# PC0_Codec.net
KiCad netlist of a schematic drawn in Altium Designer
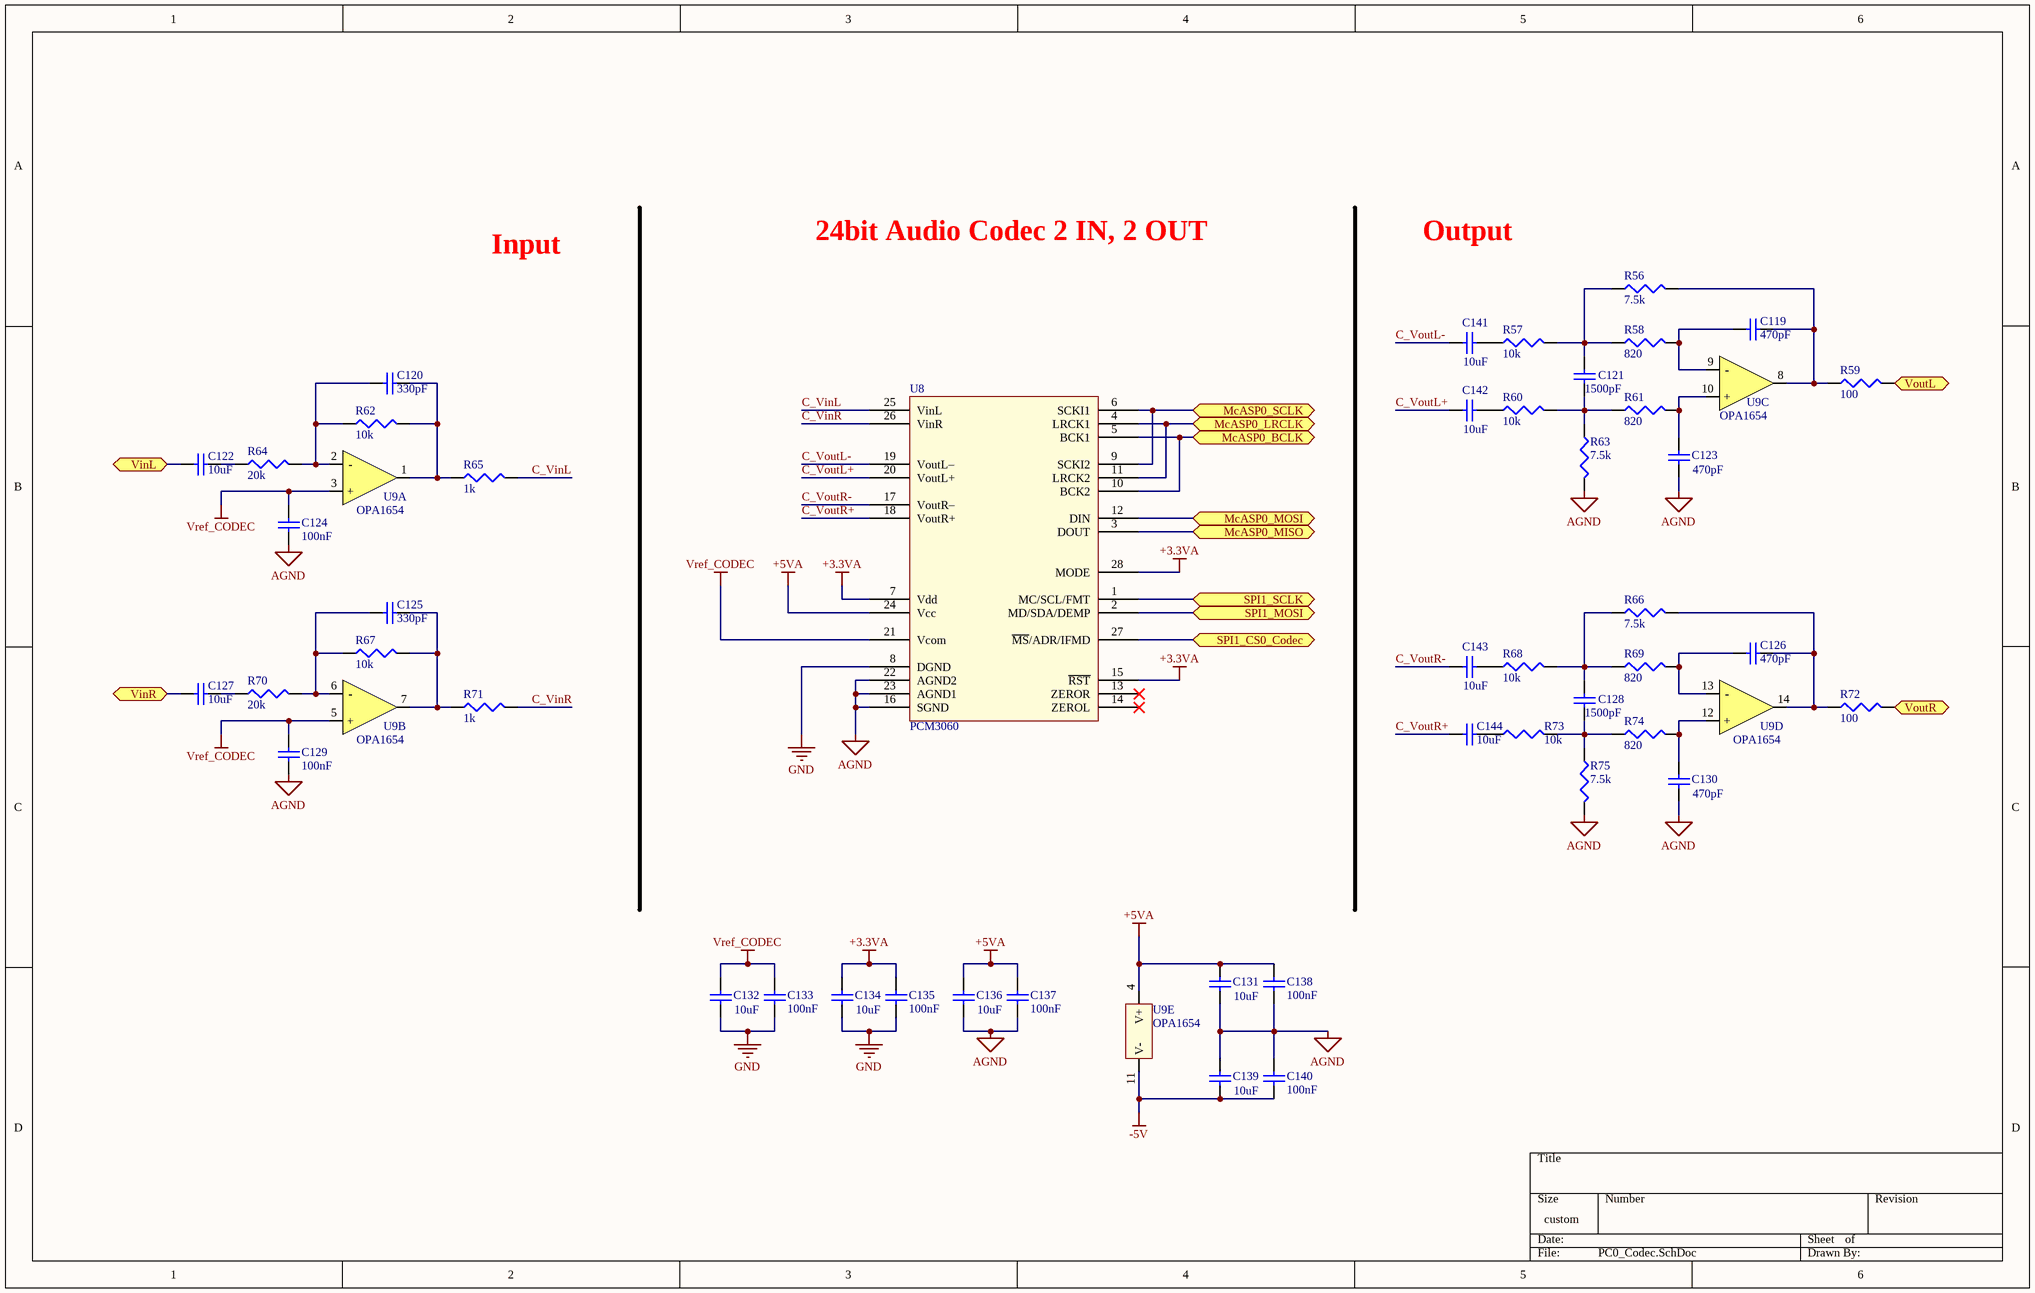
[diagram p0: PC0_Codec.SchDoc]

(export (version "E")
  (design (tool "Eeschema 10.0.6"))
  (components
    (comp (ref "C119")
      (value "470pF")
      (footprint "CAPC1608X08")
      (description "Capacitor")
      (fields (field (name "Comment") "Cap 470pF"))
      (libsource (lib "Michel") (part "Cap Semi"))
    )
    (comp (ref "C120")
      (value "330pF")
      (footprint "CAPC1608X08")
      (description "Capacitor")
      (fields (field (name "Comment") "Cap 330pF"))
      (libsource (lib "Michel") (part "Cap Semi"))
    )
    (comp (ref "C121")
      (value "1500pF")
      (footprint "CAPC1608X08")
      (description "Capacitor")
      (fields (field (name "Comment") "Cap 1500pF"))
      (libsource (lib "Michel") (part "Cap Semi"))
    )
    (comp (ref "C122")
      (value "10uF")
      (footprint "CAPC1608X08")
      (description "Capacitor")
      (fields (field (name "Comment") "Cap 10uF"))
      (libsource (lib "Michel") (part "Cap Semi"))
    )
    (comp (ref "C123")
      (value "470pF")
      (footprint "CAPC1608X08")
      (description "Capacitor")
      (fields (field (name "Comment") "Cap 470pF"))
      (libsource (lib "Michel") (part "Cap Semi"))
    )
    (comp (ref "C124")
      (value "100nF")
      (footprint "CAPC1608X08")
      (description "Capacitor")
      (fields (field (name "Comment") "Cap 100nF"))
      (libsource (lib "Michel") (part "Cap Semi"))
    )
    (comp (ref "C125")
      (value "330pF")
      (footprint "CAPC1608X08")
      (description "Capacitor")
      (fields (field (name "Comment") "Cap 330pF"))
      (libsource (lib "Michel") (part "Cap Semi"))
    )
    (comp (ref "C126")
      (value "470pF")
      (footprint "CAPC1608X08")
      (description "Capacitor")
      (fields (field (name "Comment") "Cap 470pF"))
      (libsource (lib "Michel") (part "Cap Semi"))
    )
    (comp (ref "C127")
      (value "10uF")
      (footprint "CAPC1608X08")
      (description "Capacitor")
      (fields (field (name "Comment") "Cap 10uF"))
      (libsource (lib "Michel") (part "Cap Semi"))
    )
    (comp (ref "C128")
      (value "1500pF")
      (footprint "CAPC1608X08")
      (description "Capacitor")
      (fields (field (name "Comment") "Cap 1500pF"))
      (libsource (lib "Michel") (part "Cap Semi"))
    )
    (comp (ref "C129")
      (value "100nF")
      (footprint "CAPC1608X08")
      (description "Capacitor")
      (fields (field (name "Comment") "Cap 100nF"))
      (libsource (lib "Michel") (part "Cap Semi"))
    )
    (comp (ref "C130")
      (value "470pF")
      (footprint "CAPC1608X08")
      (description "Capacitor")
      (fields (field (name "Comment") "Cap 470pF"))
      (libsource (lib "Michel") (part "Cap Semi"))
    )
    (comp (ref "C131")
      (value "10uF")
      (footprint "CAPC1608X08")
      (description "Capacitor")
      (fields (field (name "Comment") "Cap 10uF"))
      (libsource (lib "Michel") (part "Cap Semi"))
    )
    (comp (ref "C132")
      (value "10uF")
      (footprint "CAPC1608X08")
      (description "Capacitor")
      (fields (field (name "Comment") "Cap 10uF"))
      (libsource (lib "Michel") (part "Cap Semi"))
    )
    (comp (ref "C133")
      (value "100nF")
      (footprint "CAPC1608X08")
      (description "Capacitor")
      (fields (field (name "Comment") "Cap 100nF"))
      (libsource (lib "Michel") (part "Cap Semi"))
    )
    (comp (ref "C134")
      (value "10uF")
      (footprint "CAPC1608X08")
      (description "Capacitor")
      (fields (field (name "Comment") "Cap 10uF"))
      (libsource (lib "Michel") (part "Cap Semi"))
    )
    (comp (ref "C135")
      (value "100nF")
      (footprint "CAPC1608X08")
      (description "Capacitor")
      (fields (field (name "Comment") "Cap 100nF"))
      (libsource (lib "Michel") (part "Cap Semi"))
    )
    (comp (ref "C136")
      (value "10uF")
      (footprint "CAPC1608X08")
      (description "Capacitor")
      (fields (field (name "Comment") "Cap 10uF"))
      (libsource (lib "Michel") (part "Cap Semi"))
    )
    (comp (ref "C137")
      (value "100nF")
      (footprint "CAPC1608X08")
      (description "Capacitor")
      (fields (field (name "Comment") "Cap 100nF"))
      (libsource (lib "Michel") (part "Cap Semi"))
    )
    (comp (ref "C138")
      (value "100nF")
      (footprint "CAPC1608X08")
      (description "Capacitor")
      (fields (field (name "Comment") "Cap 100nF"))
      (libsource (lib "Michel") (part "Cap Semi"))
    )
    (comp (ref "C139")
      (value "10uF")
      (footprint "CAPC1608X08")
      (description "Capacitor")
      (fields (field (name "Comment") "Cap 10uF"))
      (libsource (lib "Michel") (part "Cap Semi"))
    )
    (comp (ref "C140")
      (value "100nF")
      (footprint "CAPC1608X08")
      (description "Capacitor")
      (fields (field (name "Comment") "Cap 100nF"))
      (libsource (lib "Michel") (part "Cap Semi"))
    )
    (comp (ref "C141")
      (value "10uF")
      (footprint "CAPC1608X08")
      (description "Capacitor")
      (fields (field (name "Comment") "Cap 10uF"))
      (libsource (lib "Michel") (part "Cap Semi"))
    )
    (comp (ref "C142")
      (value "10uF")
      (footprint "CAPC1608X08")
      (description "Capacitor")
      (fields (field (name "Comment") "Cap 10uF"))
      (libsource (lib "Michel") (part "Cap Semi"))
    )
    (comp (ref "C143")
      (value "10uF")
      (footprint "CAPC1608X08")
      (description "Capacitor")
      (fields (field (name "Comment") "Cap 10uF"))
      (libsource (lib "Michel") (part "Cap Semi"))
    )
    (comp (ref "C144")
      (value "10uF")
      (footprint "CAPC1608X08")
      (description "Capacitor")
      (fields (field (name "Comment") "Cap 10uF"))
      (libsource (lib "Michel") (part "Cap Semi"))
    )
    (comp (ref "R56")
      (value "7.5k")
      (footprint "RESC1608X05")
      (description "Resistor")
      (fields (field (name "Comment") "Res 7.5k"))
      (libsource (lib "Michel") (part "Res3"))
    )
    (comp (ref "R57")
      (value "10k")
      (footprint "RESC1608X05")
      (description "Resistor")
      (fields (field (name "Comment") "Res 10k"))
      (libsource (lib "Michel") (part "Res3"))
    )
    (comp (ref "R58")
      (value "820")
      (footprint "RESC1608X05")
      (description "Resistor")
      (fields (field (name "Comment") "Res 820"))
      (libsource (lib "Michel") (part "Res3"))
    )
    (comp (ref "R59")
      (value "100")
      (footprint "RESC1608X05")
      (description "Resistor")
      (fields (field (name "Comment") "Res 100"))
      (libsource (lib "Michel") (part "Res3"))
    )
    (comp (ref "R60")
      (value "10k")
      (footprint "RESC1608X05")
      (description "Resistor")
      (fields (field (name "Comment") "Res 10k"))
      (libsource (lib "Michel") (part "Res3"))
    )
    (comp (ref "R61")
      (value "820")
      (footprint "RESC1608X05")
      (description "Resistor")
      (fields (field (name "Comment") "Res 820"))
      (libsource (lib "Michel") (part "Res3"))
    )
    (comp (ref "R62")
      (value "10k")
      (footprint "RESC1608X05")
      (description "Resistor")
      (fields (field (name "Comment") "Res 10k"))
      (libsource (lib "Michel") (part "Res3"))
    )
    (comp (ref "R63")
      (value "7.5k")
      (footprint "RESC1608X05")
      (description "Resistor")
      (fields (field (name "Comment") "Res 7.5k"))
      (libsource (lib "Michel") (part "Res3"))
    )
    (comp (ref "R64")
      (value "20k")
      (footprint "RESC1608X05")
      (description "Resistor")
      (fields (field (name "Comment") "Res 20k"))
      (libsource (lib "Michel") (part "Res3"))
    )
    (comp (ref "R65")
      (value "1k")
      (footprint "RESC1608X05")
      (description "Resistor")
      (fields (field (name "Comment") "Res 1k"))
      (libsource (lib "Michel") (part "Res3"))
    )
    (comp (ref "R66")
      (value "7.5k")
      (footprint "RESC1608X05")
      (description "Resistor")
      (fields (field (name "Comment") "Res 7.5k"))
      (libsource (lib "Michel") (part "Res3"))
    )
    (comp (ref "R67")
      (value "10k")
      (footprint "RESC1608X05")
      (description "Resistor")
      (fields (field (name "Comment") "Res 10k"))
      (libsource (lib "Michel") (part "Res3"))
    )
    (comp (ref "R68")
      (value "10k")
      (footprint "RESC1608X05")
      (description "Resistor")
      (fields (field (name "Comment") "Res 10k"))
      (libsource (lib "Michel") (part "Res3"))
    )
    (comp (ref "R69")
      (value "820")
      (footprint "RESC1608X05")
      (description "Resistor")
      (fields (field (name "Comment") "Res 820"))
      (libsource (lib "Michel") (part "Res3"))
    )
    (comp (ref "R70")
      (value "20k")
      (footprint "RESC1608X05")
      (description "Resistor")
      (fields (field (name "Comment") "Res 20k"))
      (libsource (lib "Michel") (part "Res3"))
    )
    (comp (ref "R71")
      (value "1k")
      (footprint "RESC1608X05")
      (description "Resistor")
      (fields (field (name "Comment") "Res 1k"))
      (libsource (lib "Michel") (part "Res3"))
    )
    (comp (ref "R72")
      (value "100")
      (footprint "RESC1608X05")
      (description "Resistor")
      (fields (field (name "Comment") "Res 100"))
      (libsource (lib "Michel") (part "Res3"))
    )
    (comp (ref "R73")
      (value "10k")
      (footprint "RESC1608X05")
      (description "Resistor")
      (fields (field (name "Comment") "Res 10k"))
      (libsource (lib "Michel") (part "Res3"))
    )
    (comp (ref "R74")
      (value "820")
      (footprint "RESC1608X05")
      (description "Resistor")
      (fields (field (name "Comment") "Res 820"))
      (libsource (lib "Michel") (part "Res3"))
    )
    (comp (ref "R75")
      (value "7.5k")
      (footprint "RESC1608X05")
      (description "Resistor")
      (fields (field (name "Comment") "Res 7.5k"))
      (libsource (lib "Michel") (part "Res3"))
    )
    (comp (ref "U8")
      (value "PCM3060")
      (footprint "TSSOP28_PCM3060")
      (description "Stereo In/Out Audio Codec")
      (libsource (lib "Michel") (part "PCM3060"))
    )
    (comp (ref "U9")
      (value "OPA1654")
      (footprint "D14-M")
      (description "Quad Audio OpAmp")
      (libsource (lib "") (part "OPA1654_1"))
    )
  )
  (nets
    (net (code "1") (name "+3.3VA") (class "Default")
      (node (ref "C134") (pin "1") (pinfunction "1_1") (pintype "passive"))
      (node (ref "C135") (pin "2") (pinfunction "2_2") (pintype "passive"))
      (node (ref "U8") (pin "15") (pinfunction "~{RST}_15") (pintype "passive"))
      (node (ref "U8") (pin "28") (pinfunction "MODE_28") (pintype "passive"))
      (node (ref "U8") (pin "7") (pinfunction "Vdd_7") (pintype "passive"))
    )
    (net (code "2") (name "+5VA") (class "Default")
      (node (ref "C131") (pin "1") (pinfunction "1_1") (pintype "passive"))
      (node (ref "C136") (pin "1") (pinfunction "1_1") (pintype "passive"))
      (node (ref "C137") (pin "2") (pinfunction "2_2") (pintype "passive"))
      (node (ref "C138") (pin "2") (pinfunction "2_2") (pintype "passive"))
      (node (ref "U8") (pin "24") (pinfunction "Vcc_24") (pintype "passive"))
      (node (ref "U9") (pin "4") (pinfunction "V+_4") (pintype "power_in"))
    )
    (net (code "3") (name "-5V") (class "Default")
      (node (ref "C139") (pin "2") (pinfunction "2_2") (pintype "passive"))
      (node (ref "C140") (pin "1") (pinfunction "1_1") (pintype "passive"))
      (node (ref "U9") (pin "11") (pinfunction "V-_11") (pintype "power_in"))
    )
    (net (code "4") (name "/C_VinL") (class "Default")
      (node (ref "R65") (pin "2") (pinfunction "2_2") (pintype "passive"))
      (node (ref "U8") (pin "25") (pinfunction "VinL_25") (pintype "passive"))
    )
    (net (code "5") (name "/C_VinR") (class "Default")
      (node (ref "R71") (pin "2") (pinfunction "2_2") (pintype "passive"))
      (node (ref "U8") (pin "26") (pinfunction "VinR_26") (pintype "passive"))
    )
    (net (code "6") (name "/C_VoutL+") (class "Default")
      (node (ref "C142") (pin "2") (pinfunction "2_2") (pintype "passive"))
      (node (ref "U8") (pin "20") (pinfunction "VoutL+_20") (pintype "passive"))
    )
    (net (code "7") (name "/C_VoutL-") (class "Default")
      (node (ref "C141") (pin "2") (pinfunction "2_2") (pintype "passive"))
      (node (ref "U8") (pin "19") (pinfunction "VoutL–_19") (pintype "passive"))
    )
    (net (code "8") (name "/C_VoutR+") (class "Default")
      (node (ref "C144") (pin "2") (pinfunction "2_2") (pintype "passive"))
      (node (ref "U8") (pin "18") (pinfunction "VoutR+_18") (pintype "passive"))
    )
    (net (code "9") (name "/C_VoutR-") (class "Default")
      (node (ref "C143") (pin "2") (pinfunction "2_2") (pintype "passive"))
      (node (ref "U8") (pin "17") (pinfunction "VoutR–_17") (pintype "passive"))
    )
    (net (code "10") (name "/McASP0_BCLK") (class "Default")
      (node (ref "U8") (pin "10") (pinfunction "BCK2_10") (pintype "passive"))
      (node (ref "U8") (pin "5") (pinfunction "BCK1_5") (pintype "passive"))
    )
    (net (code "11") (name "/McASP0_LRCLK") (class "Default")
      (node (ref "U8") (pin "11") (pinfunction "LRCK2_11") (pintype "passive"))
      (node (ref "U8") (pin "4") (pinfunction "LRCK1_4") (pintype "passive"))
    )
    (net (code "12") (name "/McASP0_MISO") (class "Default")
      (node (ref "U8") (pin "3") (pinfunction "DOUT_3") (pintype "passive"))
    )
    (net (code "13") (name "/McASP0_MOSI") (class "Default")
      (node (ref "U8") (pin "12") (pinfunction "DIN_12") (pintype "passive"))
    )
    (net (code "14") (name "/McASP0_SCLK") (class "Default")
      (node (ref "U8") (pin "6") (pinfunction "SCKI1_6") (pintype "passive"))
      (node (ref "U8") (pin "9") (pinfunction "SCKI2_9") (pintype "passive"))
    )
    (net (code "15") (name "/SPI1_CS0_Codec") (class "Default")
      (node (ref "U8") (pin "27") (pinfunction "~{MS}/ADR/IFMD_27") (pintype "passive"))
    )
    (net (code "16") (name "/SPI1_MOSI") (class "Default")
      (node (ref "U8") (pin "2") (pinfunction "MD/SDA/DEMP_2") (pintype "passive"))
    )
    (net (code "17") (name "/SPI1_SCLK") (class "Default")
      (node (ref "U8") (pin "1") (pinfunction "MC/SCL/FMT_1") (pintype "passive"))
    )
    (net (code "18") (name "/VinL") (class "Default")
      (node (ref "C122") (pin "2") (pinfunction "2_2") (pintype "passive"))
    )
    (net (code "19") (name "/VinR") (class "Default")
      (node (ref "C127") (pin "2") (pinfunction "2_2") (pintype "passive"))
    )
    (net (code "20") (name "/VoutL") (class "Default")
      (node (ref "R59") (pin "2") (pinfunction "2_2") (pintype "passive"))
    )
    (net (code "21") (name "/VoutR") (class "Default")
      (node (ref "R72") (pin "2") (pinfunction "2_2") (pintype "passive"))
    )
    (net (code "22") (name "AGND") (class "Default")
      (node (ref "C123") (pin "2") (pinfunction "2_2") (pintype "passive"))
      (node (ref "C124") (pin "2") (pinfunction "2_2") (pintype "passive"))
      (node (ref "C129") (pin "2") (pinfunction "2_2") (pintype "passive"))
      (node (ref "C130") (pin "2") (pinfunction "2_2") (pintype "passive"))
      (node (ref "C131") (pin "2") (pinfunction "2_2") (pintype "passive"))
      (node (ref "C136") (pin "2") (pinfunction "2_2") (pintype "passive"))
      (node (ref "C137") (pin "1") (pinfunction "1_1") (pintype "passive"))
      (node (ref "C138") (pin "1") (pinfunction "1_1") (pintype "passive"))
      (node (ref "C139") (pin "1") (pinfunction "1_1") (pintype "passive"))
      (node (ref "C140") (pin "2") (pinfunction "2_2") (pintype "passive"))
      (node (ref "R63") (pin "2") (pinfunction "2_2") (pintype "passive"))
      (node (ref "R75") (pin "2") (pinfunction "2_2") (pintype "passive"))
      (node (ref "U8") (pin "16") (pinfunction "SGND_16") (pintype "passive"))
      (node (ref "U8") (pin "22") (pinfunction "AGND2_22") (pintype "passive"))
      (node (ref "U8") (pin "23") (pinfunction "AGND1_23") (pintype "passive"))
    )
    (net (code "23") (name "GND") (class "Default")
      (node (ref "C132") (pin "2") (pinfunction "2_2") (pintype "passive"))
      (node (ref "C133") (pin "1") (pinfunction "1_1") (pintype "passive"))
      (node (ref "C134") (pin "2") (pinfunction "2_2") (pintype "passive"))
      (node (ref "C135") (pin "1") (pinfunction "1_1") (pintype "passive"))
      (node (ref "U8") (pin "8") (pinfunction "DGND_8") (pintype "passive"))
    )
    (net (code "24") (name "Net-(C121-Pad1)") (class "Default")
      (node (ref "C121") (pin "1") (pinfunction "1_1") (pintype "passive"))
      (node (ref "R60") (pin "2") (pinfunction "2_2") (pintype "passive"))
      (node (ref "R61") (pin "1") (pinfunction "1_1") (pintype "passive"))
      (node (ref "R63") (pin "1") (pinfunction "1_1") (pintype "passive"))
    )
    (net (code "25") (name "Net-(C121-Pad2)") (class "Default")
      (node (ref "C121") (pin "2") (pinfunction "2_2") (pintype "passive"))
      (node (ref "R56") (pin "1") (pinfunction "1_1") (pintype "passive"))
      (node (ref "R57") (pin "2") (pinfunction "2_2") (pintype "passive"))
      (node (ref "R58") (pin "1") (pinfunction "1_1") (pintype "passive"))
    )
    (net (code "26") (name "Net-(C122-Pad1)") (class "Default")
      (node (ref "C122") (pin "1") (pinfunction "1_1") (pintype "passive"))
      (node (ref "R64") (pin "1") (pinfunction "1_1") (pintype "passive"))
    )
    (net (code "27") (name "Net-(C127-Pad1)") (class "Default")
      (node (ref "C127") (pin "1") (pinfunction "1_1") (pintype "passive"))
      (node (ref "R70") (pin "1") (pinfunction "1_1") (pintype "passive"))
    )
    (net (code "28") (name "Net-(C128-Pad1)") (class "Default")
      (node (ref "C128") (pin "1") (pinfunction "1_1") (pintype "passive"))
      (node (ref "R73") (pin "2") (pinfunction "2_2") (pintype "passive"))
      (node (ref "R74") (pin "1") (pinfunction "1_1") (pintype "passive"))
      (node (ref "R75") (pin "1") (pinfunction "1_1") (pintype "passive"))
    )
    (net (code "29") (name "Net-(C128-Pad2)") (class "Default")
      (node (ref "C128") (pin "2") (pinfunction "2_2") (pintype "passive"))
      (node (ref "R66") (pin "1") (pinfunction "1_1") (pintype "passive"))
      (node (ref "R68") (pin "2") (pinfunction "2_2") (pintype "passive"))
      (node (ref "R69") (pin "1") (pinfunction "1_1") (pintype "passive"))
    )
    (net (code "30") (name "Net-(C141-Pad1)") (class "Default")
      (node (ref "C141") (pin "1") (pinfunction "1_1") (pintype "passive"))
      (node (ref "R57") (pin "1") (pinfunction "1_1") (pintype "passive"))
    )
    (net (code "31") (name "Net-(C142-Pad1)") (class "Default")
      (node (ref "C142") (pin "1") (pinfunction "1_1") (pintype "passive"))
      (node (ref "R60") (pin "1") (pinfunction "1_1") (pintype "passive"))
    )
    (net (code "32") (name "Net-(C143-Pad1)") (class "Default")
      (node (ref "C143") (pin "1") (pinfunction "1_1") (pintype "passive"))
      (node (ref "R68") (pin "1") (pinfunction "1_1") (pintype "passive"))
    )
    (net (code "33") (name "Net-(C144-Pad1)") (class "Default")
      (node (ref "C144") (pin "1") (pinfunction "1_1") (pintype "passive"))
      (node (ref "R73") (pin "1") (pinfunction "1_1") (pintype "passive"))
    )
    (net (code "34") (name "Net-(U9A--)") (class "Default")
      (node (ref "C120") (pin "2") (pinfunction "2_2") (pintype "passive"))
      (node (ref "R62") (pin "1") (pinfunction "1_1") (pintype "passive"))
      (node (ref "R64") (pin "2") (pinfunction "2_2") (pintype "passive"))
      (node (ref "U9") (pin "2") (pinfunction "-_2") (pintype "passive"))
    )
    (net (code "35") (name "Net-(U9A-OUT)") (class "Default")
      (node (ref "C120") (pin "1") (pinfunction "1_1") (pintype "passive"))
      (node (ref "R62") (pin "2") (pinfunction "2_2") (pintype "passive"))
      (node (ref "R65") (pin "1") (pinfunction "1_1") (pintype "passive"))
      (node (ref "U9") (pin "1") (pinfunction "OUT_1") (pintype "passive"))
    )
    (net (code "36") (name "Net-(U9B--)") (class "Default")
      (node (ref "C125") (pin "2") (pinfunction "2_2") (pintype "passive"))
      (node (ref "R67") (pin "1") (pinfunction "1_1") (pintype "passive"))
      (node (ref "R70") (pin "2") (pinfunction "2_2") (pintype "passive"))
      (node (ref "U9") (pin "6") (pinfunction "-_6") (pintype "passive"))
    )
    (net (code "37") (name "Net-(U9B-OUT)") (class "Default")
      (node (ref "C125") (pin "1") (pinfunction "1_1") (pintype "passive"))
      (node (ref "R67") (pin "2") (pinfunction "2_2") (pintype "passive"))
      (node (ref "R71") (pin "1") (pinfunction "1_1") (pintype "passive"))
      (node (ref "U9") (pin "7") (pinfunction "OUT_7") (pintype "passive"))
    )
    (net (code "38") (name "Net-(U9C-+)") (class "Default")
      (node (ref "C123") (pin "1") (pinfunction "1_1") (pintype "passive"))
      (node (ref "R61") (pin "2") (pinfunction "2_2") (pintype "passive"))
      (node (ref "U9") (pin "10") (pinfunction "+_10") (pintype "passive"))
    )
    (net (code "39") (name "Net-(U9C--)") (class "Default")
      (node (ref "C119") (pin "2") (pinfunction "2_2") (pintype "passive"))
      (node (ref "R58") (pin "2") (pinfunction "2_2") (pintype "passive"))
      (node (ref "U9") (pin "9") (pinfunction "-_9") (pintype "passive"))
    )
    (net (code "40") (name "Net-(U9C-OUT)") (class "Default")
      (node (ref "C119") (pin "1") (pinfunction "1_1") (pintype "passive"))
      (node (ref "R56") (pin "2") (pinfunction "2_2") (pintype "passive"))
      (node (ref "R59") (pin "1") (pinfunction "1_1") (pintype "passive"))
      (node (ref "U9") (pin "8") (pinfunction "OUT_8") (pintype "passive"))
    )
    (net (code "41") (name "Net-(U9D-+)") (class "Default")
      (node (ref "C130") (pin "1") (pinfunction "1_1") (pintype "passive"))
      (node (ref "R74") (pin "2") (pinfunction "2_2") (pintype "passive"))
      (node (ref "U9") (pin "12") (pinfunction "+_12") (pintype "passive"))
    )
    (net (code "42") (name "Net-(U9D--)") (class "Default")
      (node (ref "C126") (pin "2") (pinfunction "2_2") (pintype "passive"))
      (node (ref "R69") (pin "2") (pinfunction "2_2") (pintype "passive"))
      (node (ref "U9") (pin "13") (pinfunction "-_13") (pintype "passive"))
    )
    (net (code "43") (name "Net-(U9D-OUT)") (class "Default")
      (node (ref "C126") (pin "1") (pinfunction "1_1") (pintype "passive"))
      (node (ref "R66") (pin "2") (pinfunction "2_2") (pintype "passive"))
      (node (ref "R72") (pin "1") (pinfunction "1_1") (pintype "passive"))
      (node (ref "U9") (pin "14") (pinfunction "OUT_14") (pintype "passive"))
    )
    (net (code "44") (name "Vref_CODEC") (class "Default")
      (node (ref "C124") (pin "1") (pinfunction "1_1") (pintype "passive"))
      (node (ref "C129") (pin "1") (pinfunction "1_1") (pintype "passive"))
      (node (ref "C132") (pin "1") (pinfunction "1_1") (pintype "passive"))
      (node (ref "C133") (pin "2") (pinfunction "2_2") (pintype "passive"))
      (node (ref "U8") (pin "21") (pinfunction "Vcom_21") (pintype "passive"))
      (node (ref "U9") (pin "3") (pinfunction "+_3") (pintype "passive"))
      (node (ref "U9") (pin "5") (pinfunction "+_5") (pintype "passive"))
    )
    (net (code "45") (name "unconnected-(U8-ZEROL-Pad14)") (class "Default")
      (node (ref "U8") (pin "14") (pinfunction "ZEROL_14") (pintype "passive+no_connect"))
    )
    (net (code "46") (name "unconnected-(U8-ZEROR-Pad13)") (class "Default")
      (node (ref "U8") (pin "13") (pinfunction "ZEROR_13") (pintype "passive+no_connect"))
    )
  )
)
